# BatteryBoard.net
KiCad netlist of a schematic drawn in Altium Designer
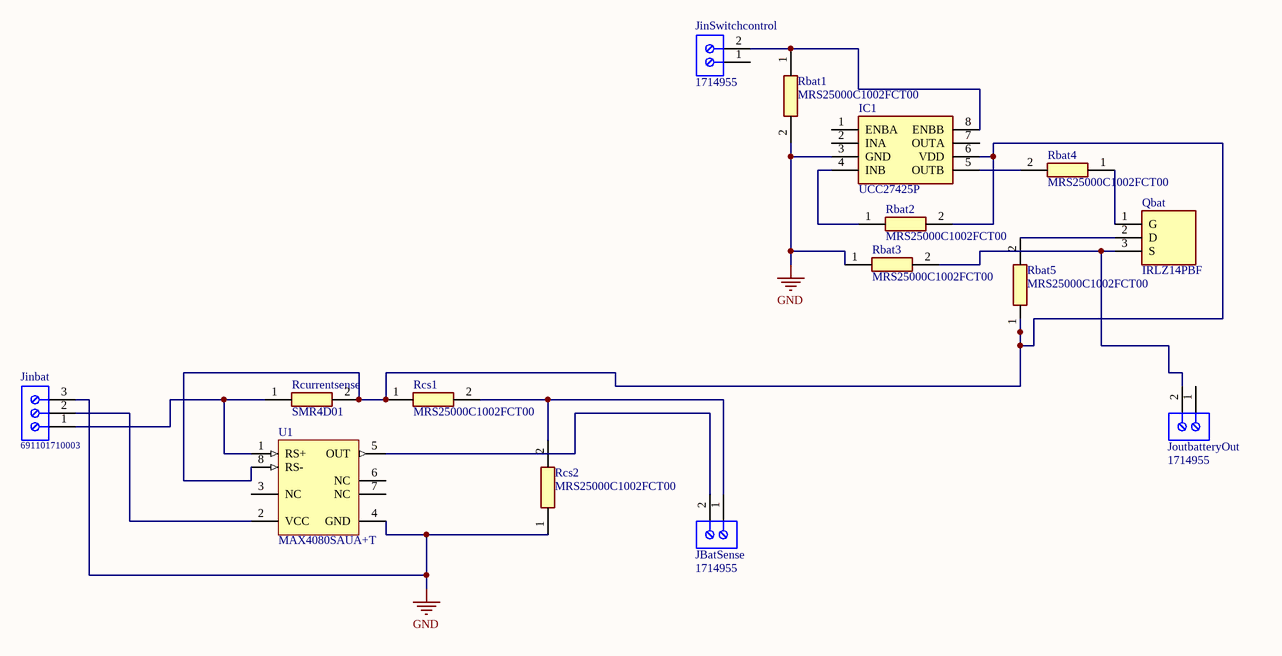
[diagram p0: BatteryBoard.SchDoc]

(export (version "E")
  (design (tool "Eeschema 10.0.6"))
  (components
    (comp (ref "IC1")
      (value "UCC27425P")
      (footprint "SamacSys:DIP794W53P254L959H508Q8N")
      (description "Integrated Circuit")
      (fields (field (name "MOUSER PART NUMBER") "595-UCC27425P"))
      (libsource (lib "*") (part "UCC27425P"))
    )
    (comp (ref "JBatSense")
      (value "1714955")
      (footprint "PHOE-1714955_V")
      (description "PC Terminal Block, Pitch 6.35 mm, 1 x 2 Position, Height 21.5 mm, Tail Lenght 5.1 mm, RoHS, Bulk")
      (fields (field (name "MANUFACTURER") "Phoenix Contact"))
      (libsource (lib "Altium Content Vault") (part "CN-1P-F-TB2"))
    )
    (comp (ref "Jinbat")
      (value "691101710003")
      (footprint "691101710003")
      (description "Series 101 - 5.00 mm Horizontal Entry Modular with Pressure Clamp WR-TBL, 3 pin")
      (fields (field (name "MANUFACTURER") "Wurth Elektronik") (field (name "PUBLISHER") "WurthElektronik"))
      (libsource (lib "Altium Content Vault") (part "WE-CN-1P-F-TB3"))
    )
    (comp (ref "JinSwitchcontrol")
      (value "1714955")
      (footprint "PHOE-1714955_V")
      (description "PC Terminal Block, Pitch 6.35 mm, 1 x 2 Position, Height 21.5 mm, Tail Lenght 5.1 mm, RoHS, Bulk")
      (fields (field (name "MANUFACTURER") "Phoenix Contact"))
      (libsource (lib "Altium Content Vault") (part "CN-1P-F-TB2"))
    )
    (comp (ref "JoutbatteryOut")
      (value "1714955")
      (footprint "PHOE-1714955_V")
      (description "PC Terminal Block, Pitch 6.35 mm, 1 x 2 Position, Height 21.5 mm, Tail Lenght 5.1 mm, RoHS, Bulk")
      (fields (field (name "MANUFACTURER") "Phoenix Contact"))
      (libsource (lib "Altium Content Vault") (part "CN-1P-F-TB2"))
    )
    (comp (ref "Qbat")
      (value "IRLZ14PBF")
      (footprint "SamacSys:TO254P465X1031X1954-3P")
      (description "Transistor")
      (fields (field (name "MOUSER PART NUMBER") "844-IRLZ14PBF"))
      (libsource (lib "*") (part "IRLZ14PBF"))
    )
    (comp (ref "Rbat1")
      (value "MRS25000C1002FCT00")
      (footprint "SamacSys:RESAD1650W60L650D250")
      (description "Resistor")
      (fields (field (name "MOUSER PART NUMBER") "594-MRS25000C1002FCT"))
      (libsource (lib "") (part "MRS25000C1002FCT00_1"))
    )
    (comp (ref "Rbat2")
      (value "MRS25000C1002FCT00")
      (footprint "SamacSys:RESAD1650W60L650D250")
      (description "Resistor")
      (fields (field (name "MOUSER PART NUMBER") "594-MRS25000C1002FCT"))
      (libsource (lib "*") (part "MRS25000C1002FCT00"))
    )
    (comp (ref "Rbat3")
      (value "MRS25000C1002FCT00")
      (footprint "SamacSys:RESAD1650W60L650D250")
      (description "Resistor")
      (fields (field (name "MOUSER PART NUMBER") "594-MRS25000C1002FCT"))
      (libsource (lib "*") (part "MRS25000C1002FCT00"))
    )
    (comp (ref "Rbat4")
      (value "MRS25000C1002FCT00")
      (footprint "SamacSys:RESAD1650W60L650D250")
      (description "Resistor")
      (fields (field (name "MOUSER PART NUMBER") "594-MRS25000C1002FCT"))
      (libsource (lib "") (part "MRS25000C1002FCT00_3"))
    )
    (comp (ref "Rbat5")
      (value "MRS25000C1002FCT00")
      (footprint "SamacSys:RESAD1650W60L650D250")
      (description "Resistor")
      (fields (field (name "MOUSER PART NUMBER") "594-MRS25000C1002FCT"))
      (libsource (lib "") (part "MRS25000C1002FCT00_2"))
    )
    (comp (ref "Rcs1")
      (value "MRS25000C1002FCT00")
      (footprint "SamacSys:RESAD1650W60L650D250")
      (description "Resistor")
      (fields (field (name "MOUSER PART NUMBER") "594-MRS25000C1002FCT"))
      (libsource (lib "*") (part "MRS25000C1002FCT00"))
    )
    (comp (ref "Rcs2")
      (value "MRS25000C1002FCT00")
      (footprint "SamacSys:RESAD1650W60L650D250")
      (description "Resistor")
      (fields (field (name "MOUSER PART NUMBER") "594-MRS25000C1002FCT"))
      (libsource (lib "") (part "MRS25000C1002FCT00_2"))
    )
    (comp (ref "Rcurrentsense")
      (value "SMR4D01")
      (footprint "SamacSys:SMR4D01")
      (description "Resistor")
      (libsource (lib "*") (part "SMR4D01"))
    )
    (comp (ref "U1")
      (value "MAX4080SAUA+T")
      (footprint "MAXM-U8+1_L")
      (libsource (lib "Altium Content Vault") (part "MAX4080-X8_1_2"))
    )
  )
  (nets
    (net (code "1") (name "GND") (class "Default")
      (node (ref "IC1") (pin "3") (pinfunction "GND_3") (pintype "passive"))
      (node (ref "Jinbat") (pin "3") (pinfunction "3_3") (pintype "passive"))
      (node (ref "Rbat1") (pin "2") (pinfunction "2_2") (pintype "passive"))
      (node (ref "Rbat3") (pin "1") (pinfunction "1_1") (pintype "passive"))
      (node (ref "Rcs2") (pin "1") (pinfunction "1_1") (pintype "passive"))
      (node (ref "U1") (pin "4") (pinfunction "GND_4") (pintype "power_in"))
    )
    (net (code "2") (name "Net-(IC1-ENBB)") (class "Default")
      (node (ref "IC1") (pin "8") (pinfunction "ENBB_8") (pintype "passive"))
      (node (ref "JinSwitchcontrol") (pin "2") (pinfunction "2_2") (pintype "passive"))
      (node (ref "Rbat1") (pin "1") (pinfunction "1_1") (pintype "passive"))
    )
    (net (code "3") (name "Net-(IC1-INB)") (class "Default")
      (node (ref "IC1") (pin "4") (pinfunction "INB_4") (pintype "passive"))
      (node (ref "Rbat2") (pin "1") (pinfunction "1_1") (pintype "passive"))
    )
    (net (code "4") (name "Net-(IC1-OUTB)") (class "Default")
      (node (ref "IC1") (pin "5") (pinfunction "OUTB_5") (pintype "passive"))
      (node (ref "Rbat4") (pin "2") (pinfunction "2_2") (pintype "passive"))
    )
    (net (code "5") (name "Net-(IC1-VDD)") (class "Default")
      (node (ref "IC1") (pin "6") (pinfunction "VDD_6") (pintype "passive"))
      (node (ref "Rbat2") (pin "2") (pinfunction "2_2") (pintype "passive"))
      (node (ref "Rbat5") (pin "1") (pinfunction "1_1") (pintype "passive"))
      (node (ref "Rcs1") (pin "1") (pinfunction "1_1") (pintype "passive"))
      (node (ref "Rcurrentsense") (pin "2") (pinfunction "2_2") (pintype "passive"))
      (node (ref "U1") (pin "8") (pinfunction "RS-_8") (pintype "input"))
    )
    (net (code "6") (name "Net-(JBatSense-Pad1)") (class "Default")
      (node (ref "JBatSense") (pin "1") (pinfunction "1_1") (pintype "passive"))
      (node (ref "Rcs1") (pin "2") (pinfunction "2_2") (pintype "passive"))
      (node (ref "Rcs2") (pin "2") (pinfunction "2_2") (pintype "passive"))
    )
    (net (code "7") (name "Net-(Qbat-D)") (class "Default")
      (node (ref "Qbat") (pin "2") (pinfunction "D_2") (pintype "passive"))
      (node (ref "Rbat5") (pin "2") (pinfunction "2_2") (pintype "passive"))
    )
    (net (code "8") (name "Net-(Qbat-G)") (class "Default")
      (node (ref "Qbat") (pin "1") (pinfunction "G_1") (pintype "passive"))
      (node (ref "Rbat4") (pin "1") (pinfunction "1_1") (pintype "passive"))
    )
    (net (code "9") (name "Net-(Qbat-S)") (class "Default")
      (node (ref "JoutbatteryOut") (pin "2") (pinfunction "2_2") (pintype "passive"))
      (node (ref "Qbat") (pin "3") (pinfunction "S_3") (pintype "passive"))
      (node (ref "Rbat3") (pin "2") (pinfunction "2_2") (pintype "passive"))
    )
    (net (code "10") (name "Net-(U1-OUT)") (class "Default")
      (node (ref "JBatSense") (pin "2") (pinfunction "2_2") (pintype "passive"))
      (node (ref "U1") (pin "5") (pinfunction "OUT_5") (pintype "output"))
    )
    (net (code "11") (name "Net-(U1-RS+)") (class "Default")
      (node (ref "Jinbat") (pin "1") (pinfunction "1_1") (pintype "passive"))
      (node (ref "Rcurrentsense") (pin "1") (pinfunction "1_1") (pintype "passive"))
      (node (ref "U1") (pin "1") (pinfunction "RS+_1") (pintype "input"))
    )
    (net (code "12") (name "Net-(U1-VCC)") (class "Default")
      (node (ref "Jinbat") (pin "2") (pinfunction "2_2") (pintype "passive"))
      (node (ref "U1") (pin "2") (pinfunction "VCC_2") (pintype "power_in"))
    )
    (net (code "13") (name "unconnected-(IC1-ENBA-Pad1)") (class "Default")
      (node (ref "IC1") (pin "1") (pinfunction "ENBA_1") (pintype "passive"))
    )
    (net (code "14") (name "unconnected-(IC1-INA-Pad2)") (class "Default")
      (node (ref "IC1") (pin "2") (pinfunction "INA_2") (pintype "passive"))
    )
    (net (code "15") (name "unconnected-(IC1-OUTA-Pad7)") (class "Default")
      (node (ref "IC1") (pin "7") (pinfunction "OUTA_7") (pintype "passive"))
    )
    (net (code "16") (name "unconnected-(JinSwitchcontrol-Pad1)") (class "Default")
      (node (ref "JinSwitchcontrol") (pin "1") (pinfunction "1_1") (pintype "passive"))
    )
    (net (code "17") (name "unconnected-(JoutbatteryOut-Pad1)") (class "Default")
      (node (ref "JoutbatteryOut") (pin "1") (pinfunction "1_1") (pintype "passive"))
    )
    (net (code "18") (name "unconnected-(U1-NC-Pad3)") (class "Default")
      (node (ref "U1") (pin "3") (pinfunction "NC_3") (pintype "passive"))
    )
    (net (code "19") (name "unconnected-(U1-NC-Pad6)") (class "Default")
      (node (ref "U1") (pin "6") (pinfunction "NC_6") (pintype "passive"))
    )
    (net (code "20") (name "unconnected-(U1-NC-Pad7)") (class "Default")
      (node (ref "U1") (pin "7") (pinfunction "NC_7") (pintype "passive"))
    )
  )
)
